# LoRa_PiHat_v_1.net
KiCad netlist of a schematic drawn in EAGLE
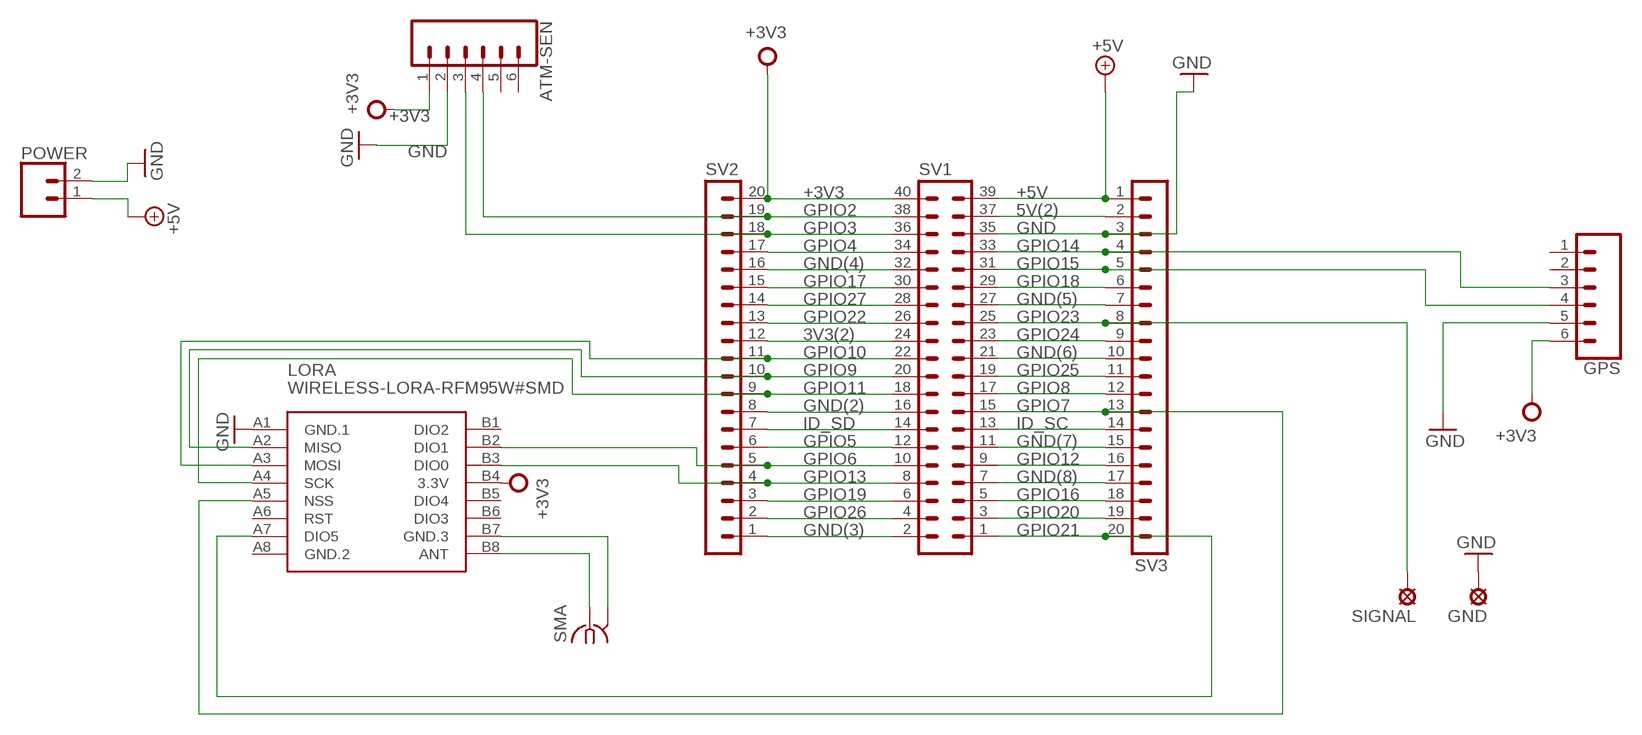
[diagram p0: schematic, sheet 1]

(export (version "E")
  (design (tool "Eeschema 10.0.6"))
  (components
    (comp (ref "ATM-SEN")
      (value "CONN_06NO_SILK_NO_POP")
      (footprint "eagle-import:1X06_NO_SILK")
      (libsource (lib "eagle-import") (part "CONN_06NO_SILK_NO_POP"))
    )
    (comp (ref "GND")
      (value "LSP10")
      (footprint "eagle-import:LSP10")
      (libsource (lib "eagle-import") (part "LSP10"))
    )
    (comp (ref "GPS")
      (value "CONN_06NO_SILK_NO_POP")
      (footprint "eagle-import:1X06_NO_SILK")
      (libsource (lib "eagle-import") (part "CONN_06NO_SILK_NO_POP"))
    )
    (comp (ref "LORA")
      (value "WIRELESS-LORA-RFM95W#SMD")
      (footprint "eagle-import:WIRELESS-LORA-RFM95W#SMD")
      (libsource (lib "eagle-import") (part "WIRELESS-LORA-RFM95W#SMD"))
    )
    (comp (ref "POWER")
      (value "CONN_02")
      (footprint "eagle-import:1X02")
      (libsource (lib "eagle-import") (part "CONN_02"))
    )
    (comp (ref "SIGNAL")
      (value "LSP10")
      (footprint "eagle-import:LSP10")
      (libsource (lib "eagle-import") (part "LSP10"))
    )
    (comp (ref "SMA")
      (value "BU-SMA-V")
      (footprint "eagle-import:BU-SMA-V")
      (libsource (lib "eagle-import") (part "BU-SMA-V"))
    )
    (comp (ref "SV1")
      (value "MA20-2")
      (footprint "eagle-import:MA20-2")
      (libsource (lib "eagle-import") (part "MA20-2"))
    )
    (comp (ref "SV2")
      (value "MA20-1L")
      (footprint "eagle-import:MA20-1L")
      (libsource (lib "eagle-import") (part "MA20-1L"))
    )
    (comp (ref "SV3")
      (value "MA20-1L")
      (footprint "eagle-import:MA20-1L")
      (libsource (lib "eagle-import") (part "MA20-1L"))
    )
  )
  (nets
    (net (code "1") (name "+3V3") (class "Default")
      (node (ref "ATM-SEN") (pin "1") (pinfunction "1_1") (pintype "passive"))
      (node (ref "GPS") (pin "6") (pinfunction "6_6") (pintype "passive"))
      (node (ref "LORA") (pin "B4") (pinfunction "3.3V_B4") (pintype "power_in"))
      (node (ref "SV1") (pin "40") (pinfunction "40_40") (pintype "passive"))
      (node (ref "SV2") (pin "20") (pinfunction "20_20") (pintype "passive"))
    )
    (net (code "2") (name "+5V") (class "Default")
      (node (ref "POWER") (pin "1") (pinfunction "1_1") (pintype "passive"))
      (node (ref "SV1") (pin "39") (pinfunction "39_39") (pintype "passive"))
      (node (ref "SV3") (pin "1") (pinfunction "1_1") (pintype "passive"))
    )
    (net (code "3") (name "/3V3(2)") (class "Default")
      (node (ref "SV1") (pin "24") (pinfunction "24_24") (pintype "passive"))
      (node (ref "SV2") (pin "12") (pinfunction "12_12") (pintype "passive"))
    )
    (net (code "4") (name "/5V(2)") (class "Default")
      (node (ref "SV1") (pin "37") (pinfunction "37_37") (pintype "passive"))
      (node (ref "SV3") (pin "2") (pinfunction "2_2") (pintype "passive"))
    )
    (net (code "5") (name "/GND(2)") (class "Default")
      (node (ref "SV1") (pin "16") (pinfunction "16_16") (pintype "passive"))
      (node (ref "SV2") (pin "8") (pinfunction "8_8") (pintype "passive"))
    )
    (net (code "6") (name "/GND(3)") (class "Default")
      (node (ref "SV1") (pin "2") (pinfunction "2_2") (pintype "passive"))
      (node (ref "SV2") (pin "1") (pinfunction "1_1") (pintype "passive"))
    )
    (net (code "7") (name "/GND(4)") (class "Default")
      (node (ref "SV1") (pin "32") (pinfunction "32_32") (pintype "passive"))
      (node (ref "SV2") (pin "16") (pinfunction "16_16") (pintype "passive"))
    )
    (net (code "8") (name "/GND(5)") (class "Default")
      (node (ref "SV1") (pin "27") (pinfunction "27_27") (pintype "passive"))
      (node (ref "SV3") (pin "7") (pinfunction "7_7") (pintype "passive"))
    )
    (net (code "9") (name "/GND(6)") (class "Default")
      (node (ref "SV1") (pin "21") (pinfunction "21_21") (pintype "passive"))
      (node (ref "SV3") (pin "10") (pinfunction "10_10") (pintype "passive"))
    )
    (net (code "10") (name "/GND(7)") (class "Default")
      (node (ref "SV1") (pin "11") (pinfunction "11_11") (pintype "passive"))
      (node (ref "SV3") (pin "15") (pinfunction "15_15") (pintype "passive"))
    )
    (net (code "11") (name "/GND(8)") (class "Default")
      (node (ref "SV1") (pin "7") (pinfunction "7_7") (pintype "passive"))
      (node (ref "SV3") (pin "17") (pinfunction "17_17") (pintype "passive"))
    )
    (net (code "12") (name "/GND.2") (class "Default")
      (node (ref "LORA") (pin "A8") (pinfunction "GND.2_A8") (pintype "power_in"))
    )
    (net (code "13") (name "/GPIO2") (class "Default")
      (node (ref "ATM-SEN") (pin "4") (pinfunction "4_4") (pintype "passive"))
      (node (ref "SV1") (pin "38") (pinfunction "38_38") (pintype "passive"))
      (node (ref "SV2") (pin "19") (pinfunction "19_19") (pintype "passive"))
    )
    (net (code "14") (name "/GPIO3") (class "Default")
      (node (ref "ATM-SEN") (pin "3") (pinfunction "3_3") (pintype "passive"))
      (node (ref "SV1") (pin "36") (pinfunction "36_36") (pintype "passive"))
      (node (ref "SV2") (pin "18") (pinfunction "18_18") (pintype "passive"))
    )
    (net (code "15") (name "/GPIO4") (class "Default")
      (node (ref "SV1") (pin "34") (pinfunction "34_34") (pintype "passive"))
      (node (ref "SV2") (pin "17") (pinfunction "17_17") (pintype "passive"))
    )
    (net (code "16") (name "/GPIO5") (class "Default")
      (node (ref "SV1") (pin "12") (pinfunction "12_12") (pintype "passive"))
      (node (ref "SV2") (pin "6") (pinfunction "6_6") (pintype "passive"))
    )
    (net (code "17") (name "/GPIO6") (class "Default")
      (node (ref "LORA") (pin "B2") (pinfunction "DIO1_B2") (pintype "bidirectional"))
      (node (ref "SV1") (pin "10") (pinfunction "10_10") (pintype "passive"))
      (node (ref "SV2") (pin "5") (pinfunction "5_5") (pintype "passive"))
    )
    (net (code "18") (name "/GPIO7") (class "Default")
      (node (ref "LORA") (pin "A5") (pinfunction "NSS_A5") (pintype "bidirectional"))
      (node (ref "SV1") (pin "15") (pinfunction "15_15") (pintype "passive"))
      (node (ref "SV3") (pin "13") (pinfunction "13_13") (pintype "passive"))
    )
    (net (code "19") (name "/GPIO8") (class "Default")
      (node (ref "SV1") (pin "17") (pinfunction "17_17") (pintype "passive"))
      (node (ref "SV3") (pin "12") (pinfunction "12_12") (pintype "passive"))
    )
    (net (code "20") (name "/GPIO9") (class "Default")
      (node (ref "LORA") (pin "A2") (pinfunction "MISO_A2") (pintype "bidirectional"))
      (node (ref "SV1") (pin "20") (pinfunction "20_20") (pintype "passive"))
      (node (ref "SV2") (pin "10") (pinfunction "10_10") (pintype "passive"))
    )
    (net (code "21") (name "/GPIO10") (class "Default")
      (node (ref "LORA") (pin "A3") (pinfunction "MOSI_A3") (pintype "bidirectional"))
      (node (ref "SV1") (pin "22") (pinfunction "22_22") (pintype "passive"))
      (node (ref "SV2") (pin "11") (pinfunction "11_11") (pintype "passive"))
    )
    (net (code "22") (name "/GPIO11") (class "Default")
      (node (ref "LORA") (pin "A4") (pinfunction "SCK_A4") (pintype "bidirectional"))
      (node (ref "SV1") (pin "18") (pinfunction "18_18") (pintype "passive"))
      (node (ref "SV2") (pin "9") (pinfunction "9_9") (pintype "passive"))
    )
    (net (code "23") (name "/GPIO12") (class "Default")
      (node (ref "SV1") (pin "9") (pinfunction "9_9") (pintype "passive"))
      (node (ref "SV3") (pin "16") (pinfunction "16_16") (pintype "passive"))
    )
    (net (code "24") (name "/GPIO13") (class "Default")
      (node (ref "LORA") (pin "B3") (pinfunction "DIO0_B3") (pintype "bidirectional"))
      (node (ref "SV1") (pin "8") (pinfunction "8_8") (pintype "passive"))
      (node (ref "SV2") (pin "4") (pinfunction "4_4") (pintype "passive"))
    )
    (net (code "25") (name "/GPIO14") (class "Default")
      (node (ref "GPS") (pin "3") (pinfunction "3_3") (pintype "passive"))
      (node (ref "SV1") (pin "33") (pinfunction "33_33") (pintype "passive"))
      (node (ref "SV3") (pin "4") (pinfunction "4_4") (pintype "passive"))
    )
    (net (code "26") (name "/GPIO15") (class "Default")
      (node (ref "GPS") (pin "4") (pinfunction "4_4") (pintype "passive"))
      (node (ref "SV1") (pin "31") (pinfunction "31_31") (pintype "passive"))
      (node (ref "SV3") (pin "5") (pinfunction "5_5") (pintype "passive"))
    )
    (net (code "27") (name "/GPIO16") (class "Default")
      (node (ref "SV1") (pin "5") (pinfunction "5_5") (pintype "passive"))
      (node (ref "SV3") (pin "18") (pinfunction "18_18") (pintype "passive"))
    )
    (net (code "28") (name "/GPIO17") (class "Default")
      (node (ref "SV1") (pin "30") (pinfunction "30_30") (pintype "passive"))
      (node (ref "SV2") (pin "15") (pinfunction "15_15") (pintype "passive"))
    )
    (net (code "29") (name "/GPIO18") (class "Default")
      (node (ref "SV1") (pin "29") (pinfunction "29_29") (pintype "passive"))
      (node (ref "SV3") (pin "6") (pinfunction "6_6") (pintype "passive"))
    )
    (net (code "30") (name "/GPIO19") (class "Default")
      (node (ref "SV1") (pin "6") (pinfunction "6_6") (pintype "passive"))
      (node (ref "SV2") (pin "3") (pinfunction "3_3") (pintype "passive"))
    )
    (net (code "31") (name "/GPIO20") (class "Default")
      (node (ref "SV1") (pin "3") (pinfunction "3_3") (pintype "passive"))
      (node (ref "SV3") (pin "19") (pinfunction "19_19") (pintype "passive"))
    )
    (net (code "32") (name "/GPIO21") (class "Default")
      (node (ref "LORA") (pin "A7") (pinfunction "DIO5_A7") (pintype "bidirectional"))
      (node (ref "SV1") (pin "1") (pinfunction "1_1") (pintype "passive"))
      (node (ref "SV3") (pin "20") (pinfunction "20_20") (pintype "passive"))
    )
    (net (code "33") (name "/GPIO22") (class "Default")
      (node (ref "SV1") (pin "26") (pinfunction "26_26") (pintype "passive"))
      (node (ref "SV2") (pin "13") (pinfunction "13_13") (pintype "passive"))
    )
    (net (code "34") (name "/GPIO23") (class "Default")
      (node (ref "SIGNAL") (pin "MP") (pinfunction "MP_MP") (pintype "passive"))
      (node (ref "SV1") (pin "25") (pinfunction "25_25") (pintype "passive"))
      (node (ref "SV3") (pin "8") (pinfunction "8_8") (pintype "passive"))
    )
    (net (code "35") (name "/GPIO24") (class "Default")
      (node (ref "SV1") (pin "23") (pinfunction "23_23") (pintype "passive"))
      (node (ref "SV3") (pin "9") (pinfunction "9_9") (pintype "passive"))
    )
    (net (code "36") (name "/GPIO25") (class "Default")
      (node (ref "SV1") (pin "19") (pinfunction "19_19") (pintype "passive"))
      (node (ref "SV3") (pin "11") (pinfunction "11_11") (pintype "passive"))
    )
    (net (code "37") (name "/GPIO26") (class "Default")
      (node (ref "SV1") (pin "4") (pinfunction "4_4") (pintype "passive"))
      (node (ref "SV2") (pin "2") (pinfunction "2_2") (pintype "passive"))
    )
    (net (code "38") (name "/GPIO27") (class "Default")
      (node (ref "SV1") (pin "28") (pinfunction "28_28") (pintype "passive"))
      (node (ref "SV2") (pin "14") (pinfunction "14_14") (pintype "passive"))
    )
    (net (code "39") (name "/ID_SC") (class "Default")
      (node (ref "SV1") (pin "13") (pinfunction "13_13") (pintype "passive"))
      (node (ref "SV3") (pin "14") (pinfunction "14_14") (pintype "passive"))
    )
    (net (code "40") (name "/ID_SD") (class "Default")
      (node (ref "SV1") (pin "14") (pinfunction "14_14") (pintype "passive"))
      (node (ref "SV2") (pin "7") (pinfunction "7_7") (pintype "passive"))
    )
    (net (code "41") (name "GND") (class "Default")
      (node (ref "ATM-SEN") (pin "2") (pinfunction "2_2") (pintype "passive"))
      (node (ref "GND") (pin "MP") (pinfunction "MP_MP") (pintype "passive"))
      (node (ref "GPS") (pin "5") (pinfunction "5_5") (pintype "passive"))
      (node (ref "LORA") (pin "A1") (pinfunction "GND.1_A1") (pintype "power_in"))
      (node (ref "POWER") (pin "2") (pinfunction "2_2") (pintype "passive"))
      (node (ref "SV1") (pin "35") (pinfunction "35_35") (pintype "passive"))
      (node (ref "SV3") (pin "3") (pinfunction "3_3") (pintype "passive"))
    )
    (net (code "42") (name "Net-(LORA-ANT)") (class "Default")
      (node (ref "LORA") (pin "B8") (pinfunction "ANT_B8") (pintype "passive"))
      (node (ref "SMA") (pin "1") (pinfunction "1_1") (pintype "passive"))
    )
    (net (code "43") (name "Net-(LORA-GND.3)") (class "Default")
      (node (ref "LORA") (pin "B7") (pinfunction "GND.3_B7") (pintype "power_in"))
      (node (ref "SMA") (pin "2") (pinfunction "2_2") (pintype "passive"))
      (node (ref "SMA") (pin "3") (pinfunction "2_3") (pintype "passive"))
      (node (ref "SMA") (pin "4") (pinfunction "2_4") (pintype "passive"))
      (node (ref "SMA") (pin "5") (pinfunction "2_5") (pintype "passive"))
    )
    (net (code "44") (name "unconnected-(ATM-SEN-Pad5)") (class "Default")
      (node (ref "ATM-SEN") (pin "5") (pinfunction "5_5") (pintype "passive"))
    )
    (net (code "45") (name "unconnected-(ATM-SEN-Pad6)") (class "Default")
      (node (ref "ATM-SEN") (pin "6") (pinfunction "6_6") (pintype "passive"))
    )
    (net (code "46") (name "unconnected-(GPS-Pad1)") (class "Default")
      (node (ref "GPS") (pin "1") (pinfunction "1_1") (pintype "passive"))
    )
    (net (code "47") (name "unconnected-(GPS-Pad2)") (class "Default")
      (node (ref "GPS") (pin "2") (pinfunction "2_2") (pintype "passive"))
    )
    (net (code "48") (name "unconnected-(LORA-DIO2-PadB1)") (class "Default")
      (node (ref "LORA") (pin "B1") (pinfunction "DIO2_B1") (pintype "bidirectional"))
    )
    (net (code "49") (name "unconnected-(LORA-DIO3-PadB6)") (class "Default")
      (node (ref "LORA") (pin "B6") (pinfunction "DIO3_B6") (pintype "bidirectional"))
    )
    (net (code "50") (name "unconnected-(LORA-DIO4-PadB5)") (class "Default")
      (node (ref "LORA") (pin "B5") (pinfunction "DIO4_B5") (pintype "bidirectional"))
    )
    (net (code "51") (name "unconnected-(LORA-RST-PadA6)") (class "Default")
      (node (ref "LORA") (pin "A6") (pinfunction "RST_A6") (pintype "bidirectional"))
    )
  )
)
